# imu_pcb.net
KiCad netlist of a schematic drawn in EAGLE
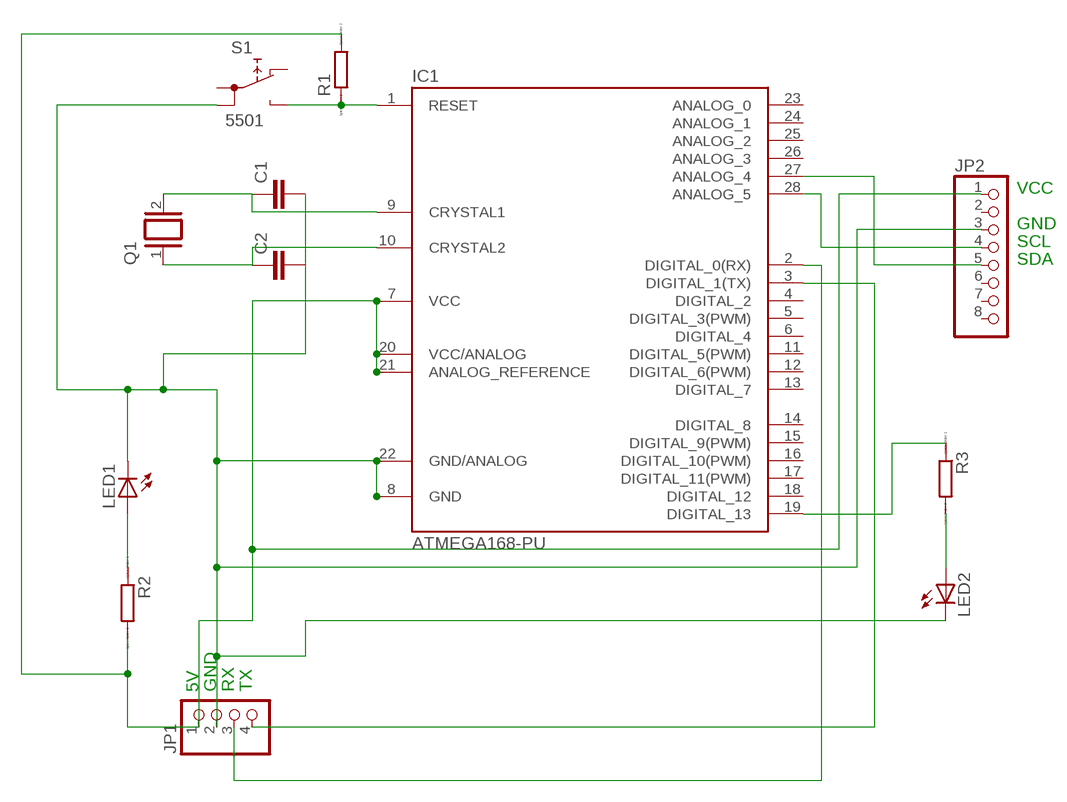
[diagram p0: schematic, sheet 1]

(export (version "E")
  (design (tool "Eeschema 10.0.6"))
  (components
    (comp (ref "C1")
      (value "C2.5/2")
      (footprint "eagle-import:C2.5-2")
      (libsource (lib "eagle-import") (part "C2.5/2"))
    )
    (comp (ref "C2")
      (value "C2.5/2")
      (footprint "eagle-import:C2.5-2")
      (libsource (lib "eagle-import") (part "C2.5/2"))
    )
    (comp (ref "IC1")
      (value "ATMEGA168-PU")
      (footprint "eagle-import:DIL28-3")
      (libsource (lib "eagle-import") (part "ATMEGA168-PU"))
    )
    (comp (ref "JP1")
      (value "PINHD-1X4")
      (footprint "eagle-import:1X04")
      (libsource (lib "eagle-import") (part "PINHD-1X4"))
    )
    (comp (ref "JP2")
      (value "PINHD-1X8")
      (footprint "eagle-import:1X08")
      (libsource (lib "eagle-import") (part "PINHD-1X8"))
    )
    (comp (ref "LED1")
      (value "LED3MM")
      (footprint "eagle-import:LED3MM")
      (libsource (lib "eagle-import") (part "LED3MM"))
    )
    (comp (ref "LED2")
      (value "LED3MM")
      (footprint "eagle-import:LED3MM")
      (libsource (lib "eagle-import") (part "LED3MM"))
    )
    (comp (ref "Q1")
      (value "XTAL/S")
      (footprint "eagle-import:QS")
      (libsource (lib "eagle-import") (part "XTAL/S"))
    )
    (comp (ref "R1")
      (value "R0204/7")
      (footprint "eagle-import:0204_7")
      (libsource (lib "eagle-import") (part "R0204/7"))
    )
    (comp (ref "R2")
      (value "R0204/7")
      (footprint "eagle-import:0204_7")
      (libsource (lib "eagle-import") (part "R0204/7"))
    )
    (comp (ref "R3")
      (value "R0204/7")
      (footprint "eagle-import:0204_7")
      (libsource (lib "eagle-import") (part "R0204/7"))
    )
    (comp (ref "S1")
      (value "5501")
      (footprint "eagle-import:5501")
      (libsource (lib "eagle-import") (part "55?01"))
    )
  )
  (nets
    (net (code "1") (name "Net-(IC1-ANALOG_4)") (class "Default")
      (node (ref "IC1") (pin "27") (pinfunction "ANALOG_4_27") (pintype "bidirectional"))
      (node (ref "JP2") (pin "5") (pinfunction "5_5") (pintype "passive"))
    )
    (net (code "2") (name "Net-(IC1-ANALOG_5)") (class "Default")
      (node (ref "IC1") (pin "28") (pinfunction "ANALOG_5_28") (pintype "bidirectional"))
      (node (ref "JP2") (pin "4") (pinfunction "4_4") (pintype "passive"))
    )
    (net (code "3") (name "Net-(IC1-ANALOG_REFERENCE)") (class "Default")
      (node (ref "IC1") (pin "20") (pinfunction "VCC/ANALOG_20") (pintype "passive"))
      (node (ref "IC1") (pin "21") (pinfunction "ANALOG_REFERENCE_21") (pintype "passive"))
      (node (ref "IC1") (pin "7") (pinfunction "VCC_7") (pintype "power_in"))
      (node (ref "JP1") (pin "1") (pinfunction "1_1") (pintype "passive"))
      (node (ref "JP2") (pin "1") (pinfunction "1_1") (pintype "passive"))
      (node (ref "R1") (pin "2") (pinfunction "2_2") (pintype "passive"))
      (node (ref "R2") (pin "2") (pinfunction "2_2") (pintype "passive"))
    )
    (net (code "4") (name "Net-(IC1-CRYSTAL1)") (class "Default")
      (node (ref "C1") (pin "1") (pinfunction "1_1") (pintype "passive"))
      (node (ref "IC1") (pin "9") (pinfunction "CRYSTAL1_9") (pintype "bidirectional"))
      (node (ref "Q1") (pin "2") (pinfunction "2_2") (pintype "passive"))
    )
    (net (code "5") (name "Net-(IC1-CRYSTAL2)") (class "Default")
      (node (ref "C2") (pin "1") (pinfunction "1_1") (pintype "passive"))
      (node (ref "IC1") (pin "10") (pinfunction "CRYSTAL2_10") (pintype "bidirectional"))
      (node (ref "Q1") (pin "1") (pinfunction "1_1") (pintype "passive"))
    )
    (net (code "6") (name "Net-(IC1-DIGITAL_0(RX))") (class "Default")
      (node (ref "IC1") (pin "2") (pinfunction "DIGITAL_0(RX)_2") (pintype "bidirectional"))
      (node (ref "JP1") (pin "3") (pinfunction "3_3") (pintype "passive"))
    )
    (net (code "7") (name "Net-(IC1-DIGITAL_1(TX))") (class "Default")
      (node (ref "IC1") (pin "3") (pinfunction "DIGITAL_1(TX)_3") (pintype "bidirectional"))
      (node (ref "JP1") (pin "4") (pinfunction "4_4") (pintype "passive"))
    )
    (net (code "8") (name "Net-(IC1-DIGITAL_13)") (class "Default")
      (node (ref "IC1") (pin "19") (pinfunction "DIGITAL_13_19") (pintype "bidirectional"))
      (node (ref "R3") (pin "1") (pinfunction "1_1") (pintype "passive"))
    )
    (net (code "9") (name "Net-(IC1-GND)") (class "Default")
      (node (ref "C1") (pin "2") (pinfunction "2_2") (pintype "passive"))
      (node (ref "C2") (pin "2") (pinfunction "2_2") (pintype "passive"))
      (node (ref "IC1") (pin "22") (pinfunction "GND/ANALOG_22") (pintype "power_in"))
      (node (ref "IC1") (pin "8") (pinfunction "GND_8") (pintype "power_in"))
      (node (ref "JP1") (pin "2") (pinfunction "2_2") (pintype "passive"))
      (node (ref "JP2") (pin "3") (pinfunction "3_3") (pintype "passive"))
      (node (ref "LED1") (pin "K") (pinfunction "C_K") (pintype "passive"))
      (node (ref "LED2") (pin "K") (pinfunction "C_K") (pintype "passive"))
      (node (ref "S1") (pin "1B") (pinfunction "1B_1B") (pintype "passive"))
    )
    (net (code "10") (name "Net-(IC1-RESET)") (class "Default")
      (node (ref "IC1") (pin "1") (pinfunction "RESET_1") (pintype "bidirectional"))
      (node (ref "R1") (pin "1") (pinfunction "1_1") (pintype "passive"))
      (node (ref "S1") (pin "NO") (pinfunction "NO_NO") (pintype "passive"))
    )
    (net (code "11") (name "Net-(LED1-PadA)") (class "Default")
      (node (ref "LED1") (pin "A") (pinfunction "A_A") (pintype "passive"))
      (node (ref "R2") (pin "1") (pinfunction "1_1") (pintype "passive"))
    )
    (net (code "12") (name "Net-(LED2-PadA)") (class "Default")
      (node (ref "LED2") (pin "A") (pinfunction "A_A") (pintype "passive"))
      (node (ref "R3") (pin "2") (pinfunction "2_2") (pintype "passive"))
    )
    (net (code "13") (name "unconnected-(IC1-ANALOG_0-Pad23)") (class "Default")
      (node (ref "IC1") (pin "23") (pinfunction "ANALOG_0_23") (pintype "bidirectional"))
    )
    (net (code "14") (name "unconnected-(IC1-ANALOG_1-Pad24)") (class "Default")
      (node (ref "IC1") (pin "24") (pinfunction "ANALOG_1_24") (pintype "bidirectional"))
    )
    (net (code "15") (name "unconnected-(IC1-ANALOG_2-Pad25)") (class "Default")
      (node (ref "IC1") (pin "25") (pinfunction "ANALOG_2_25") (pintype "bidirectional"))
    )
    (net (code "16") (name "unconnected-(IC1-ANALOG_3-Pad26)") (class "Default")
      (node (ref "IC1") (pin "26") (pinfunction "ANALOG_3_26") (pintype "bidirectional"))
    )
    (net (code "17") (name "unconnected-(IC1-DIGITAL_2-Pad4)") (class "Default")
      (node (ref "IC1") (pin "4") (pinfunction "DIGITAL_2_4") (pintype "bidirectional"))
    )
    (net (code "18") (name "unconnected-(IC1-DIGITAL_3(PWM)-Pad5)") (class "Default")
      (node (ref "IC1") (pin "5") (pinfunction "DIGITAL_3(PWM)_5") (pintype "bidirectional"))
    )
    (net (code "19") (name "unconnected-(IC1-DIGITAL_4-Pad6)") (class "Default")
      (node (ref "IC1") (pin "6") (pinfunction "DIGITAL_4_6") (pintype "bidirectional"))
    )
    (net (code "20") (name "unconnected-(IC1-DIGITAL_5(PWM)-Pad11)") (class "Default")
      (node (ref "IC1") (pin "11") (pinfunction "DIGITAL_5(PWM)_11") (pintype "bidirectional"))
    )
    (net (code "21") (name "unconnected-(IC1-DIGITAL_6(PWM)-Pad12)") (class "Default")
      (node (ref "IC1") (pin "12") (pinfunction "DIGITAL_6(PWM)_12") (pintype "bidirectional"))
    )
    (net (code "22") (name "unconnected-(IC1-DIGITAL_7-Pad13)") (class "Default")
      (node (ref "IC1") (pin "13") (pinfunction "DIGITAL_7_13") (pintype "bidirectional"))
    )
    (net (code "23") (name "unconnected-(IC1-DIGITAL_8-Pad14)") (class "Default")
      (node (ref "IC1") (pin "14") (pinfunction "DIGITAL_8_14") (pintype "bidirectional"))
    )
    (net (code "24") (name "unconnected-(IC1-DIGITAL_9(PWM)-Pad15)") (class "Default")
      (node (ref "IC1") (pin "15") (pinfunction "DIGITAL_9(PWM)_15") (pintype "bidirectional"))
    )
    (net (code "25") (name "unconnected-(IC1-DIGITAL_10(PWM)-Pad16)") (class "Default")
      (node (ref "IC1") (pin "16") (pinfunction "DIGITAL_10(PWM)_16") (pintype "bidirectional"))
    )
    (net (code "26") (name "unconnected-(IC1-DIGITAL_11(PWM)-Pad17)") (class "Default")
      (node (ref "IC1") (pin "17") (pinfunction "DIGITAL_11(PWM)_17") (pintype "bidirectional"))
    )
    (net (code "27") (name "unconnected-(IC1-DIGITAL_12-Pad18)") (class "Default")
      (node (ref "IC1") (pin "18") (pinfunction "DIGITAL_12_18") (pintype "bidirectional"))
    )
    (net (code "28") (name "unconnected-(JP2-Pad2)") (class "Default")
      (node (ref "JP2") (pin "2") (pinfunction "2_2") (pintype "passive"))
    )
    (net (code "29") (name "unconnected-(JP2-Pad6)") (class "Default")
      (node (ref "JP2") (pin "6") (pinfunction "6_6") (pintype "passive"))
    )
    (net (code "30") (name "unconnected-(JP2-Pad7)") (class "Default")
      (node (ref "JP2") (pin "7") (pinfunction "7_7") (pintype "passive"))
    )
    (net (code "31") (name "unconnected-(JP2-Pad8)") (class "Default")
      (node (ref "JP2") (pin "8") (pinfunction "8_8") (pintype "passive"))
    )
    (net (code "32") (name "unconnected-(S1-Pad1A)") (class "Default")
      (node (ref "S1") (pin "1A") (pinfunction "1A_1A") (pintype "passive"))
    )
    (net (code "33") (name "unconnected-(S1-PadNC)") (class "Default")
      (node (ref "S1") (pin "NC") (pinfunction "NC_NC") (pintype "passive"))
    )
  )
)
